# gps_fe_v5.net
KiCad netlist of a schematic drawn in EAGLE
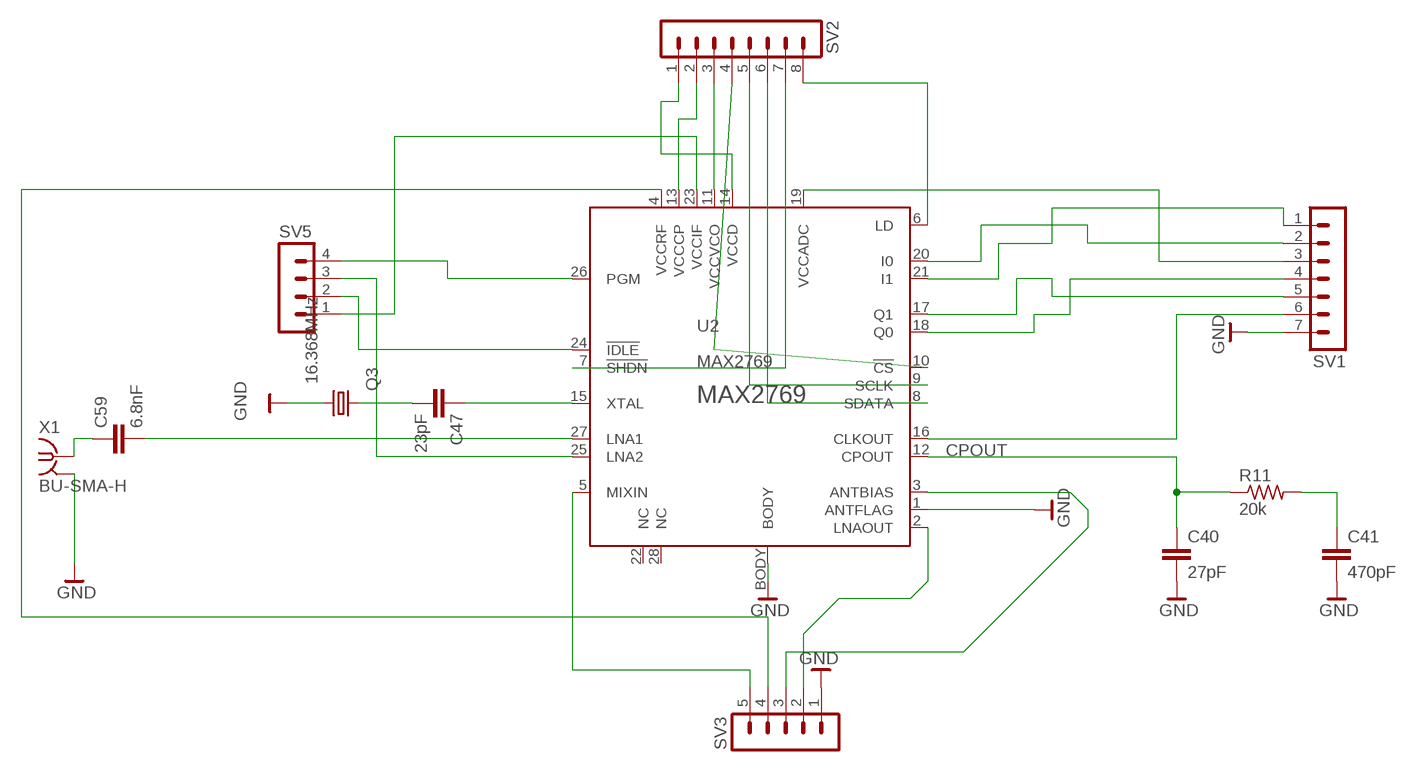
[diagram p0: schematic, sheet 1]

(export (version "E")
  (design (tool "Eeschema 10.0.6"))
  (components
    (comp (ref "C40")
      (value "27pF")
      (footprint "eagle-import:C0402")
      (libsource (lib "eagle-import") (part "C-EUC0402"))
    )
    (comp (ref "C41")
      (value "470pF")
      (footprint "eagle-import:C0402")
      (libsource (lib "eagle-import") (part "C-EUC0402"))
    )
    (comp (ref "C47")
      (value "23pF")
      (footprint "eagle-import:C0402")
      (libsource (lib "eagle-import") (part "C-EUC0402"))
    )
    (comp (ref "C59")
      (value "6.8nF")
      (footprint "eagle-import:C0402")
      (libsource (lib "eagle-import") (part "C-EUC0402"))
    )
    (comp (ref "Q3")
      (value "16.368MHz")
      (footprint "eagle-import:CTS406")
      (libsource (lib "eagle-import") (part "CRYSTALCTS406"))
    )
    (comp (ref "R11")
      (value "20k")
      (footprint "eagle-import:R0402")
      (libsource (lib "eagle-import") (part "R-US_R0402"))
    )
    (comp (ref "SV1")
      (value "MA07-1")
      (footprint "eagle-import:MA07-1")
      (libsource (lib "eagle-import") (part "MA07-1"))
    )
    (comp (ref "SV2")
      (value "MA08-1")
      (footprint "eagle-import:MA08-1")
      (libsource (lib "eagle-import") (part "MA08-1"))
    )
    (comp (ref "SV3")
      (value "MA05-1")
      (footprint "eagle-import:MA05-1")
      (libsource (lib "eagle-import") (part "MA05-1"))
    )
    (comp (ref "SV5")
      (value "MA04-1")
      (footprint "eagle-import:MA04-1")
      (libsource (lib "eagle-import") (part "MA04-1"))
    )
    (comp (ref "U2")
      (value "MAX2769")
      (footprint "eagle-import:90-0023")
      (libsource (lib "eagle-import") (part "MAX2769"))
    )
    (comp (ref "X1")
      (value "BU-SMA-H")
      (footprint "eagle-import:BU-SMA-H")
      (libsource (lib "eagle-import") (part "BU-SMA-H"))
    )
  )
  (nets
    (net (code "1") (name "/CPOUT") (class "Default")
      (node (ref "C40") (pin "1") (pinfunction "1_1") (pintype "passive"))
      (node (ref "R11") (pin "1") (pinfunction "1_1") (pintype "passive"))
      (node (ref "U2") (pin "12") (pinfunction "CPOUT_12") (pintype "passive"))
    )
    (net (code "2") (name "GND") (class "Default")
      (node (ref "C40") (pin "2") (pinfunction "2_2") (pintype "passive"))
      (node (ref "C41") (pin "2") (pinfunction "2_2") (pintype "passive"))
      (node (ref "Q3") (pin "3") (pinfunction "2_3") (pintype "passive"))
      (node (ref "SV1") (pin "7") (pinfunction "7_7") (pintype "passive"))
      (node (ref "SV3") (pin "1") (pinfunction "1_1") (pintype "passive"))
      (node (ref "U2") (pin "1") (pinfunction "ANTFLAG_1") (pintype "output"))
      (node (ref "U2") (pin "BODY") (pinfunction "BODY_BODY") (pintype "power_in"))
      (node (ref "X1") (pin "2") (pinfunction "GND_2") (pintype "power_in"))
    )
    (net (code "3") (name "Net-(C41-Pad1)") (class "Default")
      (node (ref "C41") (pin "1") (pinfunction "1_1") (pintype "passive"))
      (node (ref "R11") (pin "2") (pinfunction "2_2") (pintype "passive"))
    )
    (net (code "4") (name "Net-(C47-Pad2)") (class "Default")
      (node (ref "C47") (pin "2") (pinfunction "2_2") (pintype "passive"))
      (node (ref "Q3") (pin "1") (pinfunction "1_1") (pintype "passive"))
    )
    (net (code "5") (name "Net-(C59-Pad1)") (class "Default")
      (node (ref "C59") (pin "1") (pinfunction "1_1") (pintype "passive"))
      (node (ref "X1") (pin "1") (pinfunction "1_1") (pintype "passive"))
    )
    (net (code "6") (name "Net-(U2-ANTBIAS)") (class "Default")
      (node (ref "SV3") (pin "3") (pinfunction "3_3") (pintype "passive"))
      (node (ref "U2") (pin "3") (pinfunction "ANTBIAS_3") (pintype "output"))
    )
    (net (code "7") (name "Net-(U2-CLKOUT)") (class "Default")
      (node (ref "SV1") (pin "6") (pinfunction "6_6") (pintype "passive"))
      (node (ref "U2") (pin "16") (pinfunction "CLKOUT_16") (pintype "output"))
    )
    (net (code "8") (name "Net-(U2-I0)") (class "Default")
      (node (ref "SV1") (pin "2") (pinfunction "2_2") (pintype "passive"))
      (node (ref "U2") (pin "20") (pinfunction "I0_20") (pintype "output"))
    )
    (net (code "9") (name "Net-(U2-I1)") (class "Default")
      (node (ref "SV1") (pin "1") (pinfunction "1_1") (pintype "passive"))
      (node (ref "U2") (pin "21") (pinfunction "I1_21") (pintype "output"))
    )
    (net (code "10") (name "Net-(U2-LD)") (class "Default")
      (node (ref "SV2") (pin "8") (pinfunction "8_8") (pintype "passive"))
      (node (ref "U2") (pin "6") (pinfunction "LD_6") (pintype "output"))
    )
    (net (code "11") (name "Net-(U2-LNA1)") (class "Default")
      (node (ref "C59") (pin "2") (pinfunction "2_2") (pintype "passive"))
      (node (ref "U2") (pin "27") (pinfunction "LNA1_27") (pintype "passive"))
    )
    (net (code "12") (name "Net-(U2-LNA2)") (class "Default")
      (node (ref "SV5") (pin "3") (pinfunction "3_3") (pintype "passive"))
      (node (ref "U2") (pin "25") (pinfunction "LNA2_25") (pintype "passive"))
    )
    (net (code "13") (name "Net-(U2-LNAOUT)") (class "Default")
      (node (ref "SV3") (pin "2") (pinfunction "2_2") (pintype "passive"))
      (node (ref "U2") (pin "2") (pinfunction "LNAOUT_2") (pintype "passive"))
    )
    (net (code "14") (name "Net-(U2-MIXIN)") (class "Default")
      (node (ref "SV3") (pin "5") (pinfunction "5_5") (pintype "passive"))
      (node (ref "U2") (pin "5") (pinfunction "MIXIN_5") (pintype "passive"))
    )
    (net (code "15") (name "Net-(U2-PGM)") (class "Default")
      (node (ref "SV5") (pin "4") (pinfunction "4_4") (pintype "passive"))
      (node (ref "U2") (pin "26") (pinfunction "PGM_26") (pintype "input"))
    )
    (net (code "16") (name "Net-(U2-Q0)") (class "Default")
      (node (ref "SV1") (pin "4") (pinfunction "4_4") (pintype "passive"))
      (node (ref "U2") (pin "18") (pinfunction "Q0_18") (pintype "output"))
    )
    (net (code "17") (name "Net-(U2-Q1)") (class "Default")
      (node (ref "SV1") (pin "5") (pinfunction "5_5") (pintype "passive"))
      (node (ref "U2") (pin "17") (pinfunction "Q1_17") (pintype "output"))
    )
    (net (code "18") (name "Net-(U2-SCLK)") (class "Default")
      (node (ref "SV2") (pin "5") (pinfunction "5_5") (pintype "passive"))
      (node (ref "U2") (pin "9") (pinfunction "SCLK_9") (pintype "input"))
    )
    (net (code "19") (name "Net-(U2-SDATA)") (class "Default")
      (node (ref "SV2") (pin "6") (pinfunction "6_6") (pintype "passive"))
      (node (ref "U2") (pin "8") (pinfunction "SDATA_8") (pintype "bidirectional"))
    )
    (net (code "20") (name "Net-(U2-VCCADC)") (class "Default")
      (node (ref "SV1") (pin "3") (pinfunction "3_3") (pintype "passive"))
      (node (ref "U2") (pin "19") (pinfunction "VCCADC_19") (pintype "power_in"))
    )
    (net (code "21") (name "Net-(U2-VCCCP)") (class "Default")
      (node (ref "SV2") (pin "2") (pinfunction "2_2") (pintype "passive"))
      (node (ref "U2") (pin "13") (pinfunction "VCCCP_13") (pintype "power_in"))
    )
    (net (code "22") (name "Net-(U2-VCCD)") (class "Default")
      (node (ref "SV2") (pin "1") (pinfunction "1_1") (pintype "passive"))
      (node (ref "U2") (pin "14") (pinfunction "VCCD_14") (pintype "power_in"))
    )
    (net (code "23") (name "Net-(U2-VCCIF)") (class "Default")
      (node (ref "SV5") (pin "1") (pinfunction "1_1") (pintype "passive"))
      (node (ref "U2") (pin "23") (pinfunction "VCCIF_23") (pintype "power_in"))
    )
    (net (code "24") (name "Net-(U2-VCCRF)") (class "Default")
      (node (ref "SV3") (pin "4") (pinfunction "4_4") (pintype "passive"))
      (node (ref "U2") (pin "4") (pinfunction "VCCRF_4") (pintype "power_in"))
    )
    (net (code "25") (name "Net-(U2-VCCVCO)") (class "Default")
      (node (ref "SV2") (pin "3") (pinfunction "3_3") (pintype "passive"))
      (node (ref "U2") (pin "11") (pinfunction "VCCVCO_11") (pintype "power_in"))
    )
    (net (code "26") (name "Net-(U2-XTAL)") (class "Default")
      (node (ref "C47") (pin "1") (pinfunction "1_1") (pintype "passive"))
      (node (ref "U2") (pin "15") (pinfunction "XTAL_15") (pintype "input"))
    )
    (net (code "27") (name "Net-(U2-~{CS})") (class "Default")
      (node (ref "SV2") (pin "4") (pinfunction "4_4") (pintype "passive"))
      (node (ref "U2") (pin "10") (pinfunction "~{CS}_10") (pintype "input"))
    )
    (net (code "28") (name "Net-(U2-~{IDLE})") (class "Default")
      (node (ref "SV5") (pin "2") (pinfunction "2_2") (pintype "passive"))
      (node (ref "U2") (pin "24") (pinfunction "~{IDLE}_24") (pintype "input"))
    )
    (net (code "29") (name "Net-(U2-~{SHDN})") (class "Default")
      (node (ref "SV2") (pin "7") (pinfunction "7_7") (pintype "passive"))
      (node (ref "U2") (pin "7") (pinfunction "~{SHDN}_7") (pintype "input"))
    )
    (net (code "30") (name "unconnected-(U2-NC-Pad22)") (class "Default")
      (node (ref "U2") (pin "22") (pinfunction "NC_22") (pintype "no_connect"))
    )
    (net (code "31") (name "unconnected-(U2-NC-Pad28)") (class "Default")
      (node (ref "U2") (pin "28") (pinfunction "NC_28") (pintype "no_connect"))
    )
  )
)
